# gyro.net
KiCad netlist of a schematic drawn in EAGLE
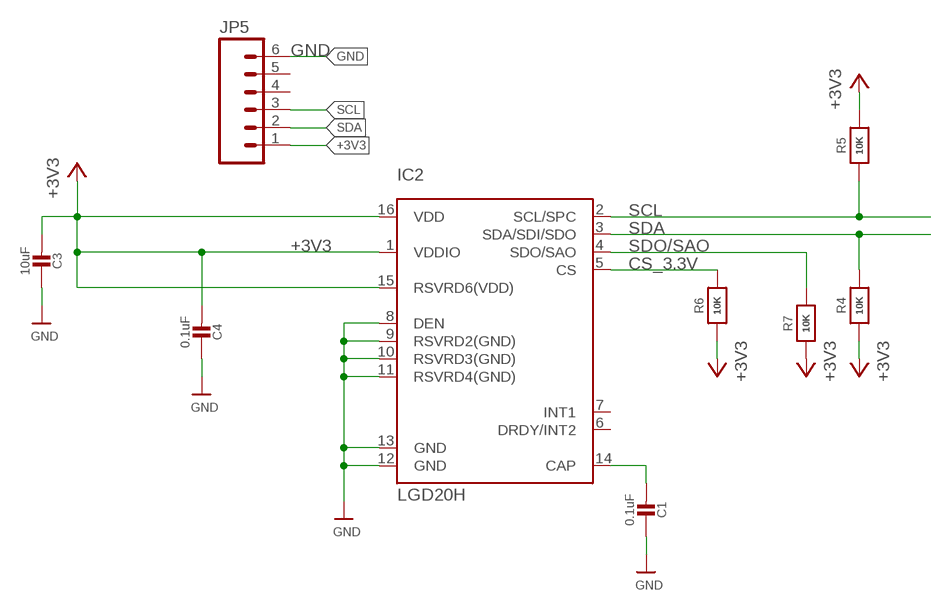
[diagram p0: schematic, sheet 1]

(export (version "E")
  (design (tool "Eeschema 10.0.6"))
  (components
    (comp (ref "C1")
      (value "0.1uF")
      (footprint "eagle-import:0805-NO")
      (libsource (lib "eagle-import") (part "CAP_CERAMIC0805-NOOUTLINE"))
    )
    (comp (ref "C3")
      (value "10uF")
      (footprint "eagle-import:0805-NO")
      (libsource (lib "eagle-import") (part "CAP_CERAMIC0805-NOOUTLINE"))
    )
    (comp (ref "C4")
      (value "0.1uF")
      (footprint "eagle-import:0805-NO")
      (libsource (lib "eagle-import") (part "CAP_CERAMIC0805-NOOUTLINE"))
    )
    (comp (ref "IC2")
      (value "LGD20H")
      (footprint "eagle-import:L3GD20H_LGA16L")
      (libsource (lib "eagle-import") (part "GYRO_L3GD20H"))
    )
    (comp (ref "JP5")
      (value "M06SIP")
      (footprint "eagle-import:1X06")
      (libsource (lib "eagle-import") (part "M06SIP"))
    )
    (comp (ref "R4")
      (value "10K")
      (footprint "eagle-import:0805-NO")
      (libsource (lib "eagle-import") (part "RESISTOR0805_NOOUTLINE"))
    )
    (comp (ref "R5")
      (value "10K")
      (footprint "eagle-import:0805-NO")
      (libsource (lib "eagle-import") (part "RESISTOR0805_NOOUTLINE"))
    )
    (comp (ref "R6")
      (value "10K")
      (footprint "eagle-import:_0805MP")
      (libsource (lib "eagle-import") (part "RESISTOR_0805MP"))
    )
    (comp (ref "R7")
      (value "10K")
      (footprint "eagle-import:0805-NO")
      (libsource (lib "eagle-import") (part "RESISTOR0805_NOOUTLINE"))
    )
  )
  (nets
    (net (code "1") (name "+3V3") (class "Default")
      (node (ref "C3") (pin "2") (pinfunction "2_2") (pintype "passive"))
      (node (ref "C4") (pin "2") (pinfunction "2_2") (pintype "passive"))
      (node (ref "IC2") (pin "1") (pinfunction "VDDIO_1") (pintype "power_in"))
      (node (ref "IC2") (pin "15") (pinfunction "RSVRD6(VDD)_15") (pintype "bidirectional"))
      (node (ref "IC2") (pin "16") (pinfunction "VDD_16") (pintype "bidirectional"))
      (node (ref "JP5") (pin "1") (pinfunction "1_1") (pintype "passive"))
      (node (ref "R4") (pin "1") (pinfunction "1_1") (pintype "passive"))
      (node (ref "R5") (pin "2") (pinfunction "2_2") (pintype "passive"))
      (node (ref "R6") (pin "1") (pinfunction "1_1") (pintype "passive"))
      (node (ref "R7") (pin "1") (pinfunction "1_1") (pintype "passive"))
    )
    (net (code "2") (name "/CS_3.3V") (class "Default")
      (node (ref "IC2") (pin "5") (pinfunction "CS_5") (pintype "bidirectional"))
      (node (ref "R6") (pin "2") (pinfunction "2_2") (pintype "passive"))
    )
    (net (code "3") (name "/SDO{slash}SAO") (class "Default")
      (node (ref "IC2") (pin "4") (pinfunction "SDO/SAO_4") (pintype "bidirectional"))
      (node (ref "R7") (pin "2") (pinfunction "2_2") (pintype "passive"))
    )
    (net (code "4") (name "GND") (class "Default")
      (node (ref "C1") (pin "1") (pinfunction "1_1") (pintype "passive"))
      (node (ref "C3") (pin "1") (pinfunction "1_1") (pintype "passive"))
      (node (ref "C4") (pin "1") (pinfunction "1_1") (pintype "passive"))
      (node (ref "IC2") (pin "10") (pinfunction "RSVRD3(GND)_10") (pintype "bidirectional"))
      (node (ref "IC2") (pin "11") (pinfunction "RSVRD4(GND)_11") (pintype "bidirectional"))
      (node (ref "IC2") (pin "12") (pinfunction "GND_12") (pintype "bidirectional"))
      (node (ref "IC2") (pin "13") (pinfunction "GND_13") (pintype "bidirectional"))
      (node (ref "IC2") (pin "8") (pinfunction "DEN_8") (pintype "bidirectional"))
      (node (ref "IC2") (pin "9") (pinfunction "RSVRD2(GND)_9") (pintype "bidirectional"))
      (node (ref "JP5") (pin "6") (pinfunction "6_6") (pintype "passive"))
    )
    (net (code "5") (name "Net-(IC2-CAP)") (class "Default")
      (node (ref "C1") (pin "2") (pinfunction "2_2") (pintype "passive"))
      (node (ref "IC2") (pin "14") (pinfunction "CAP_14") (pintype "bidirectional"))
    )
    (net (code "6") (name "SCL") (class "Default")
      (node (ref "IC2") (pin "2") (pinfunction "SCL/SPC_2") (pintype "bidirectional"))
      (node (ref "JP5") (pin "3") (pinfunction "3_3") (pintype "passive"))
      (node (ref "R5") (pin "1") (pinfunction "1_1") (pintype "passive"))
    )
    (net (code "7") (name "SDA") (class "Default")
      (node (ref "IC2") (pin "3") (pinfunction "SDA/SDI/SDO_3") (pintype "bidirectional"))
      (node (ref "JP5") (pin "2") (pinfunction "2_2") (pintype "passive"))
      (node (ref "R4") (pin "2") (pinfunction "2_2") (pintype "passive"))
    )
    (net (code "8") (name "unconnected-(IC2-DRDY{slash}INT2-Pad6)") (class "Default")
      (node (ref "IC2") (pin "6") (pinfunction "DRDY/INT2_6") (pintype "bidirectional"))
    )
    (net (code "9") (name "unconnected-(IC2-INT1-Pad7)") (class "Default")
      (node (ref "IC2") (pin "7") (pinfunction "INT1_7") (pintype "bidirectional"))
    )
    (net (code "10") (name "unconnected-(JP5-Pad4)") (class "Default")
      (node (ref "JP5") (pin "4") (pinfunction "4_4") (pintype "passive"))
    )
    (net (code "11") (name "unconnected-(JP5-Pad5)") (class "Default")
      (node (ref "JP5") (pin "5") (pinfunction "5_5") (pintype "passive"))
    )
  )
)
